# SmashBall.net
KiCad netlist of a schematic drawn in EAGLE
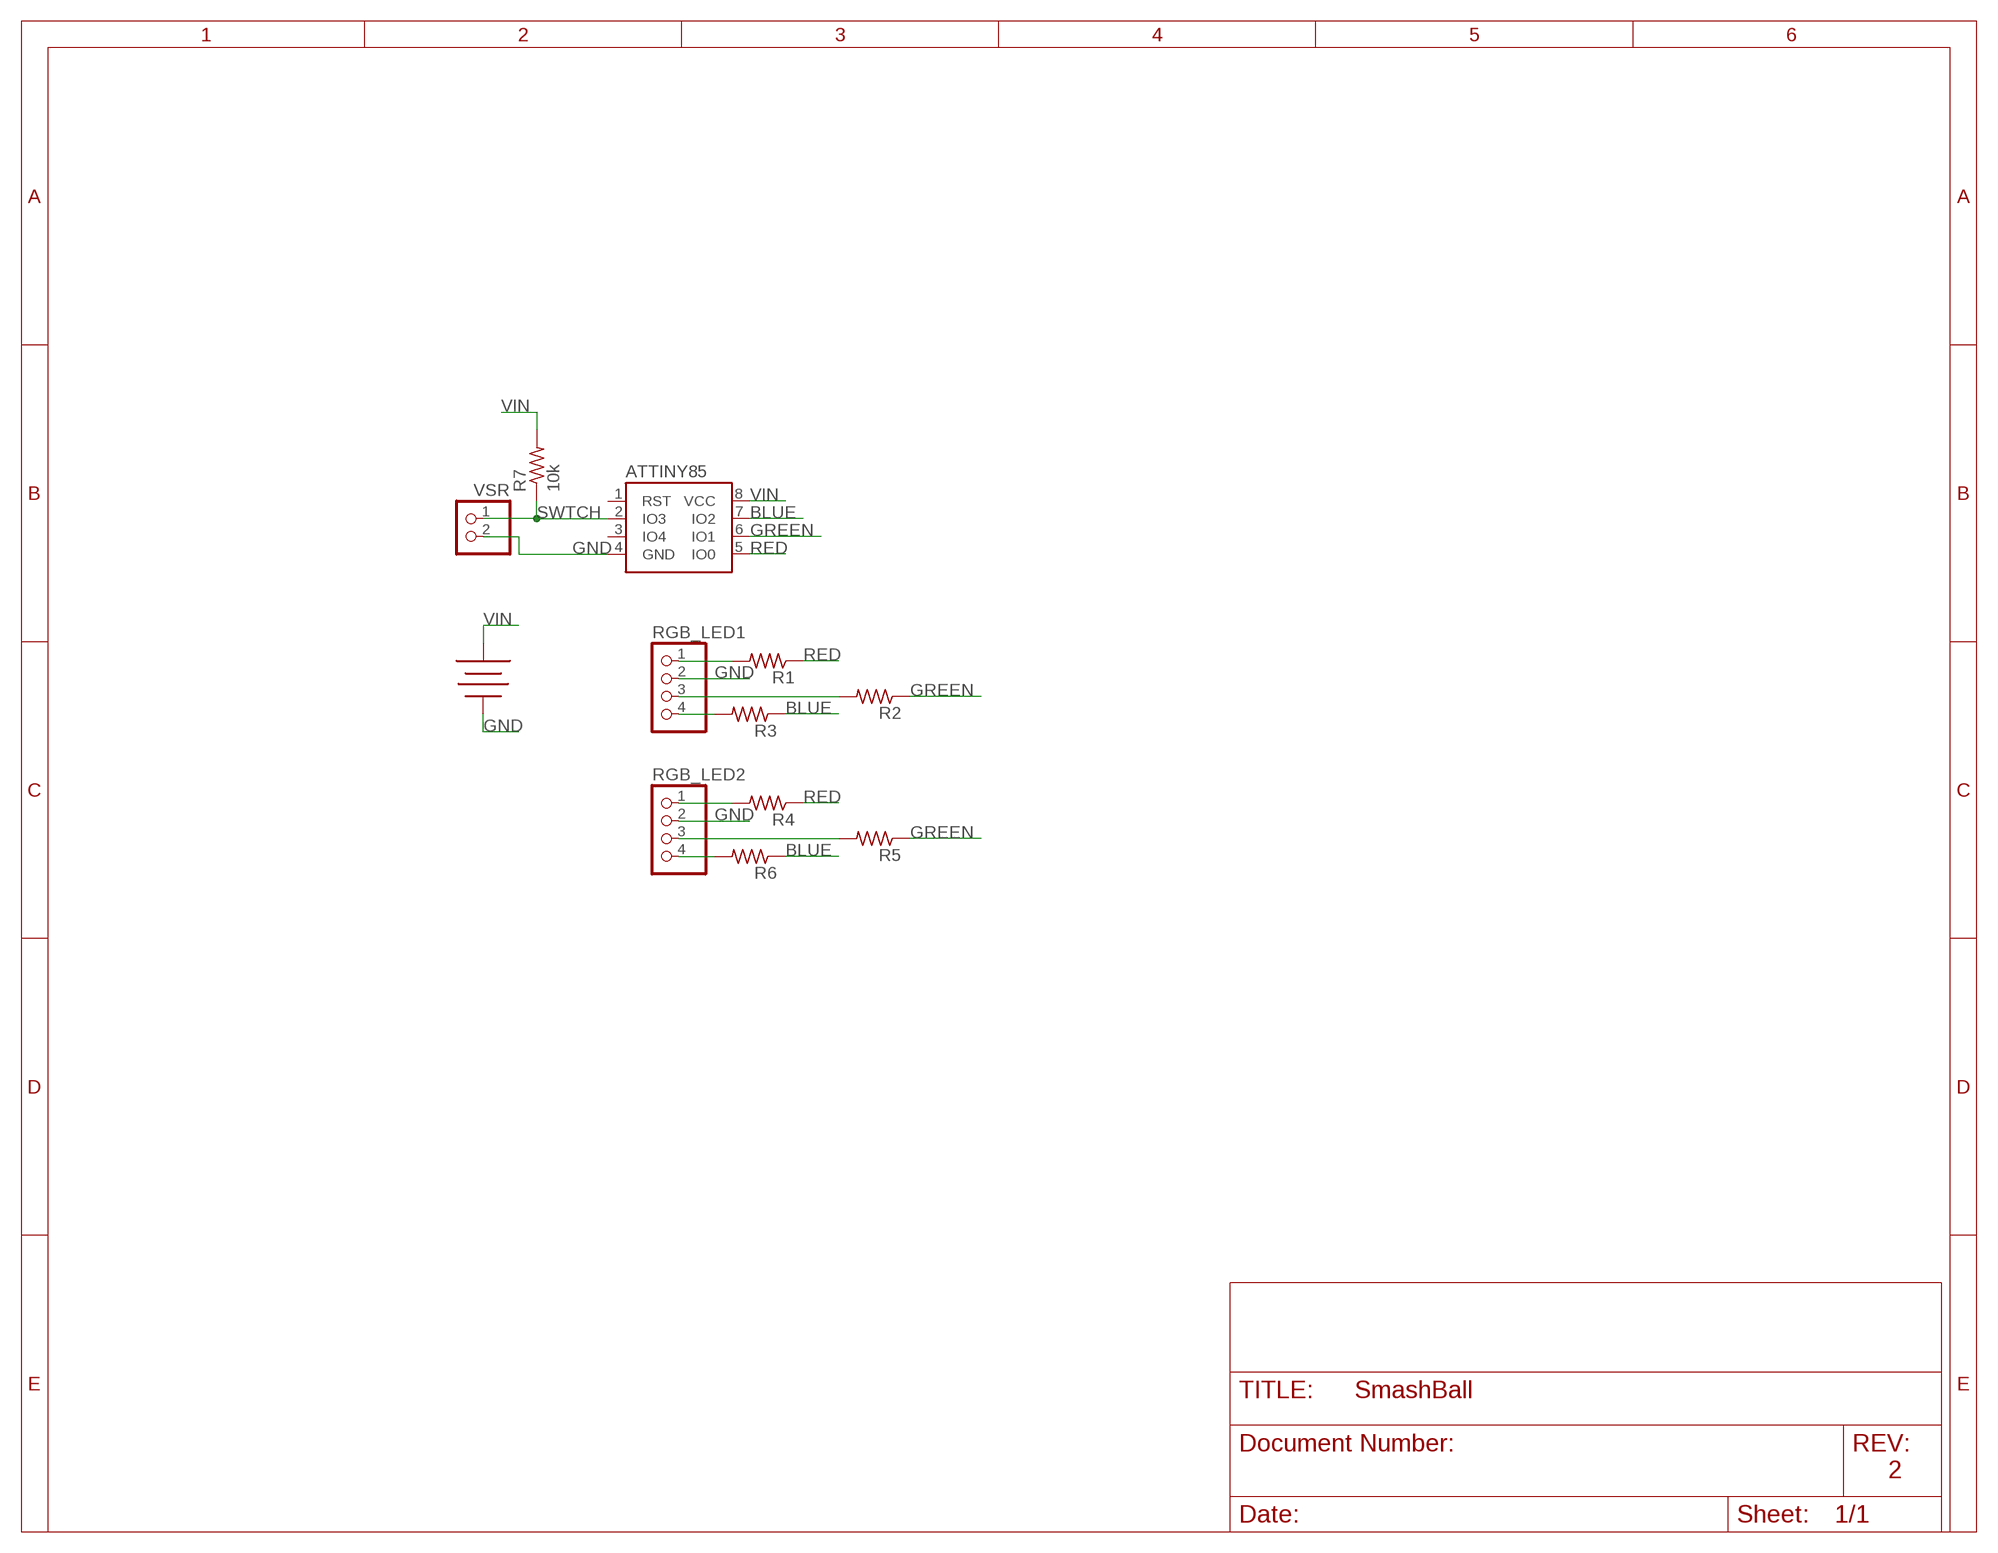
[diagram p0: schematic, sheet 1]

(export (version "E")
  (design (tool "Eeschema 10.0.6"))
  (components
    (comp (ref "R1")
      (value "R-US_0207/2V")
      (footprint "eagle-import:0207_2V")
      (libsource (lib "eagle-import") (part "R-US_0207/2V"))
    )
    (comp (ref "R2")
      (value "R-US_0207/2V")
      (footprint "eagle-import:0207_2V")
      (libsource (lib "eagle-import") (part "R-US_0207/2V"))
    )
    (comp (ref "R3")
      (value "R-US_0207/2V")
      (footprint "eagle-import:0207_2V")
      (libsource (lib "eagle-import") (part "R-US_0207/2V"))
    )
    (comp (ref "R4")
      (value "R-US_0207/2V")
      (footprint "eagle-import:0207_2V")
      (libsource (lib "eagle-import") (part "R-US_0207/2V"))
    )
    (comp (ref "R5")
      (value "R-US_0207/2V")
      (footprint "eagle-import:0207_2V")
      (libsource (lib "eagle-import") (part "R-US_0207/2V"))
    )
    (comp (ref "R6")
      (value "R-US_0207/2V")
      (footprint "eagle-import:0207_2V")
      (libsource (lib "eagle-import") (part "R-US_0207/2V"))
    )
    (comp (ref "R7")
      (value "10k")
      (footprint "eagle-import:0207_2V")
      (libsource (lib "eagle-import") (part "R-US_0207/2V"))
    )
    (comp (ref "RGB_LED1")
      (value "PINHD-1X4")
      (footprint "eagle-import:1X04")
      (libsource (lib "eagle-import") (part "PINHD-1X4"))
    )
    (comp (ref "RGB_LED2")
      (value "PINHD-1X4")
      (footprint "eagle-import:1X04")
      (libsource (lib "eagle-import") (part "PINHD-1X4"))
    )
    (comp (ref "U$1")
      (value "ATTINY85")
      (footprint "eagle-import:DIP762W53P254L950H370Q8B")
      (libsource (lib "eagle-import") (part "ATTINY85"))
    )
    (comp (ref "U$2")
      (value "2032-BATTERY")
      (footprint "eagle-import:2032-BATT")
      (libsource (lib "eagle-import") (part "2032-BATTERY"))
    )
    (comp (ref "VSR")
      (value "PINHD-1X2")
      (footprint "eagle-import:1X02")
      (libsource (lib "eagle-import") (part "PINHD-1X2"))
    )
  )
  (nets
    (net (code "1") (name "/BLUE") (class "Default")
      (node (ref "R3") (pin "1") (pinfunction "1_1") (pintype "passive"))
      (node (ref "R6") (pin "1") (pinfunction "1_1") (pintype "passive"))
      (node (ref "U$1") (pin "7") (pinfunction "IO2_7") (pintype "bidirectional"))
    )
    (net (code "2") (name "/GND") (class "Default")
      (node (ref "RGB_LED1") (pin "2") (pinfunction "2_2") (pintype "passive"))
      (node (ref "RGB_LED2") (pin "2") (pinfunction "2_2") (pintype "passive"))
      (node (ref "U$1") (pin "4") (pinfunction "GND_4") (pintype "bidirectional"))
      (node (ref "U$2") (pin "GND") (pinfunction "GND_GND") (pintype "bidirectional"))
      (node (ref "VSR") (pin "2") (pinfunction "2_2") (pintype "passive"))
    )
    (net (code "3") (name "/GREEN") (class "Default")
      (node (ref "R2") (pin "1") (pinfunction "1_1") (pintype "passive"))
      (node (ref "R5") (pin "1") (pinfunction "1_1") (pintype "passive"))
      (node (ref "U$1") (pin "6") (pinfunction "IO1_6") (pintype "bidirectional"))
    )
    (net (code "4") (name "/RED") (class "Default")
      (node (ref "R1") (pin "1") (pinfunction "1_1") (pintype "passive"))
      (node (ref "R4") (pin "1") (pinfunction "1_1") (pintype "passive"))
      (node (ref "U$1") (pin "5") (pinfunction "IO0_5") (pintype "bidirectional"))
    )
    (net (code "5") (name "/SWTCH") (class "Default")
      (node (ref "R7") (pin "1") (pinfunction "1_1") (pintype "passive"))
      (node (ref "U$1") (pin "2") (pinfunction "IO3_2") (pintype "bidirectional"))
      (node (ref "VSR") (pin "1") (pinfunction "1_1") (pintype "passive"))
    )
    (net (code "6") (name "/VIN") (class "Default")
      (node (ref "R7") (pin "2") (pinfunction "2_2") (pintype "passive"))
      (node (ref "U$1") (pin "8") (pinfunction "VCC_8") (pintype "bidirectional"))
      (node (ref "U$2") (pin "VCC") (pinfunction "VCC_VCC") (pintype "bidirectional"))
    )
    (net (code "7") (name "Net-(R1-Pad2)") (class "Default")
      (node (ref "R1") (pin "2") (pinfunction "2_2") (pintype "passive"))
      (node (ref "RGB_LED1") (pin "1") (pinfunction "1_1") (pintype "passive"))
    )
    (net (code "8") (name "Net-(R2-Pad2)") (class "Default")
      (node (ref "R2") (pin "2") (pinfunction "2_2") (pintype "passive"))
      (node (ref "RGB_LED1") (pin "3") (pinfunction "3_3") (pintype "passive"))
    )
    (net (code "9") (name "Net-(R3-Pad2)") (class "Default")
      (node (ref "R3") (pin "2") (pinfunction "2_2") (pintype "passive"))
      (node (ref "RGB_LED1") (pin "4") (pinfunction "4_4") (pintype "passive"))
    )
    (net (code "10") (name "Net-(R4-Pad2)") (class "Default")
      (node (ref "R4") (pin "2") (pinfunction "2_2") (pintype "passive"))
      (node (ref "RGB_LED2") (pin "1") (pinfunction "1_1") (pintype "passive"))
    )
    (net (code "11") (name "Net-(R5-Pad2)") (class "Default")
      (node (ref "R5") (pin "2") (pinfunction "2_2") (pintype "passive"))
      (node (ref "RGB_LED2") (pin "3") (pinfunction "3_3") (pintype "passive"))
    )
    (net (code "12") (name "Net-(R6-Pad2)") (class "Default")
      (node (ref "R6") (pin "2") (pinfunction "2_2") (pintype "passive"))
      (node (ref "RGB_LED2") (pin "4") (pinfunction "4_4") (pintype "passive"))
    )
    (net (code "13") (name "unconnected-(U$1-IO4-Pad3)") (class "Default")
      (node (ref "U$1") (pin "3") (pinfunction "IO4_3") (pintype "bidirectional"))
    )
    (net (code "14") (name "unconnected-(U$1-RST-Pad1)") (class "Default")
      (node (ref "U$1") (pin "1") (pinfunction "RST_1") (pintype "bidirectional"))
    )
  )
)
